# Sheet3_Power_Managment.net
KiCad netlist of a schematic drawn in Altium Designer
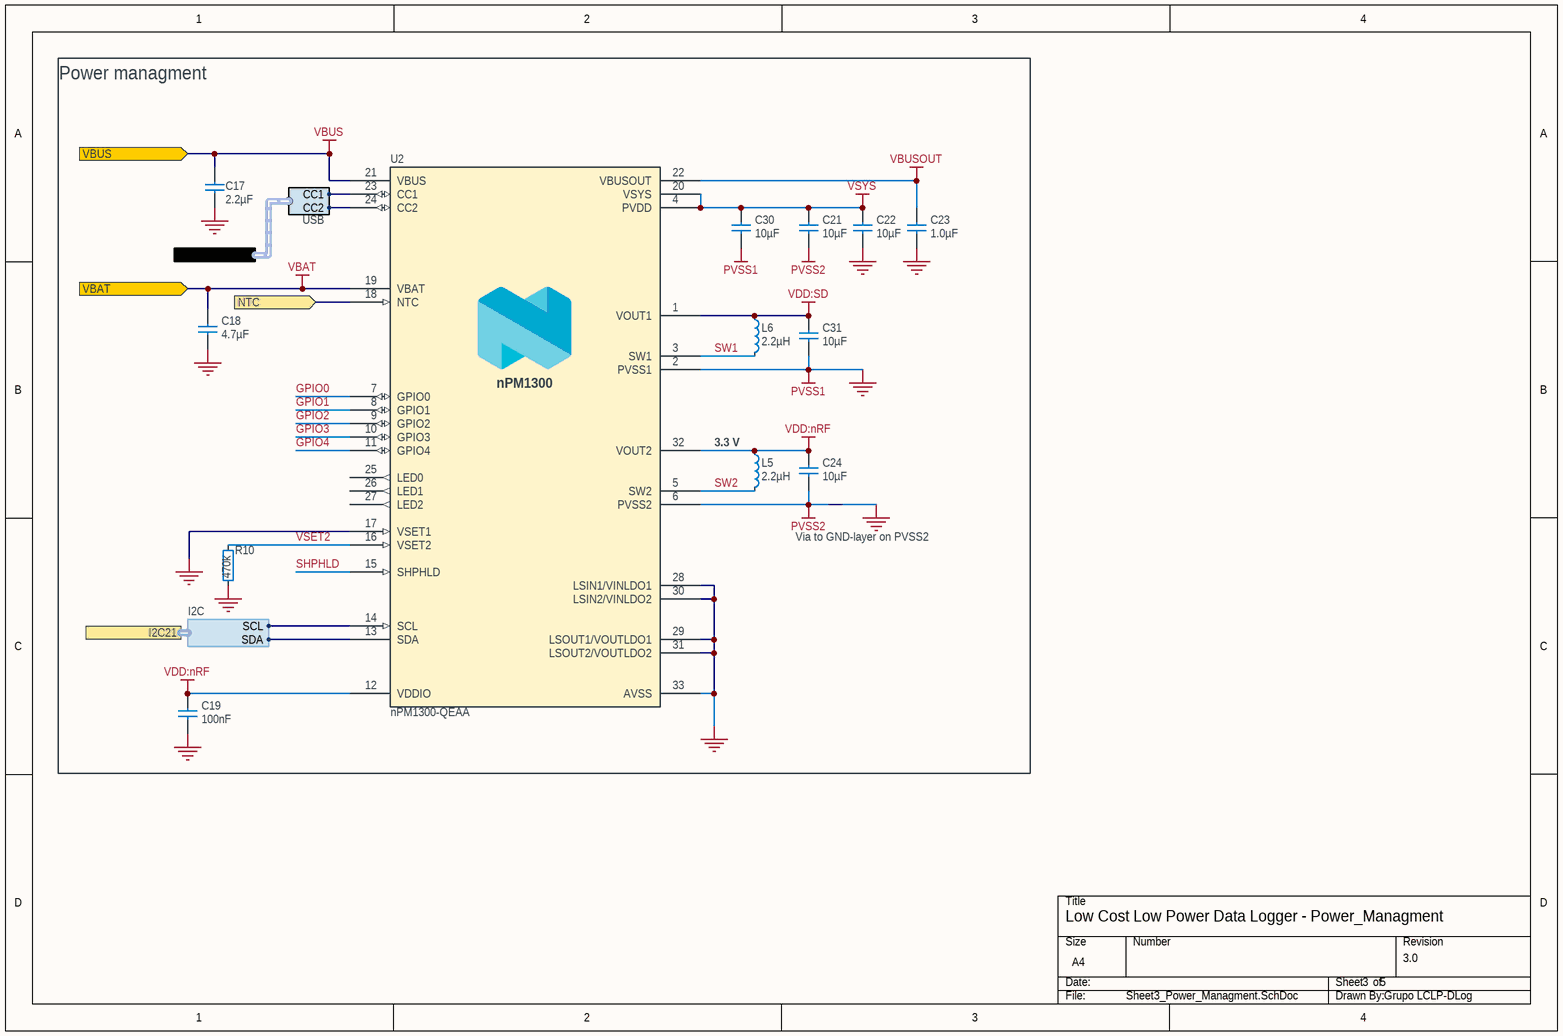
[diagram p0: Sheet3_Power_Managment.SchDoc]

(export (version "E")
  (design (tool "Eeschema 10.0.6"))
  (components
    (comp (ref "C17")
      (value "2.2µF")
      (footprint "LCLP:CAPC1005X04L")
      (description "Capacitor, X5R, ±10%")
      (fields
        (field (name "PART NUMBER") "C0402-2µ2-10V")
        (field (name "MANUFACTURER") "N.A.")
        (field (name "AUTHOR") "rsk")
      )
      (libsource (lib "") (part "CAP_1"))
    )
    (comp (ref "C18")
      (value "4.7µF")
      (footprint "LCLP:CAPC1608X06L")
      (description "Capacitor, Ceramic, X5R, ±10%, 10V")
      (fields
        (field (name "PART NUMBER") "C0603-4µ7-10V-X5R")
        (field (name "MANUFACTURER") "N.A.")
        (field (name "AUTHOR") "rubr")
      )
      (libsource (lib "") (part "CAP_1"))
    )
    (comp (ref "C19")
      (value "100nF")
      (footprint "LCLP:CAPC0603X03L_C")
      (description "Capacitor, X5R, ±10%, 100nF, 16V")
      (fields
        (field (name "PART NUMBER") "C0201-100n")
        (field (name "MANUFACTURER") "N.A.")
        (field (name "AUTHOR") "rsk")
      )
      (libsource (lib "AltiumLib") (part "CAP"))
    )
    (comp (ref "C21")
      (value "10µF")
      (footprint "LCLP:CAPC1608X06L")
      (description "Capacitor, X5R, ±20%")
      (fields
        (field (name "PART NUMBER") "C0603-10µ")
        (field (name "MANUFACTURER") "N.A.")
        (field (name "AUTHOR") "rsk")
      )
      (libsource (lib "AltiumLib") (part "CAP"))
    )
    (comp (ref "C22")
      (value "10µF")
      (footprint "LCLP:CAPC1608X06L")
      (description "Capacitor, X5R, ±20%")
      (fields
        (field (name "PART NUMBER") "C0603-10µ")
        (field (name "MANUFACTURER") "N.A.")
        (field (name "AUTHOR") "rsk")
      )
      (libsource (lib "AltiumLib") (part "CAP"))
    )
    (comp (ref "C23")
      (value "1.0µF")
      (footprint "LCLP:CAPC1608X06L")
      (description "Capacitor, Ceramic, 1.0µF 10V X5R 0603,±10%")
      (fields
        (field (name "PART NUMBER") "C0603-1µ0-10V-X5R")
        (field (name "MANUFACTURER") "N.A.")
        (field (name "AUTHOR") "getr")
      )
      (libsource (lib "AltiumLib") (part "CAP"))
    )
    (comp (ref "C24")
      (value "10µF")
      (footprint "LCLP:CAPC1608X06L")
      (description "Capacitor, X5R, ±20%")
      (fields
        (field (name "PART NUMBER") "C0603-10µ")
        (field (name "MANUFACTURER") "N.A.")
        (field (name "AUTHOR") "rsk")
      )
      (libsource (lib "AltiumLib") (part "CAP"))
    )
    (comp (ref "C30")
      (value "10µF")
      (footprint "LCLP:CAPC1608X06L")
      (description "Capacitor, Ceramic, X5R, ±20%, 25V")
      (fields
        (field (name "PART NUMBER") "C0603-10µ-25V-X5R-GRM188R61E106MA73J")
        (field (name "MANUFACTURER") "Murata")
        (field (name "AUTHOR") "rsk")
      )
      (libsource (lib "") (part "CAP_1"))
    )
    (comp (ref "C31")
      (value "10µF")
      (footprint "LCLP:CAPC1608X06L")
      (description "Capacitor, Ceramic, X5R, ±20%, 25V")
      (fields
        (field (name "PART NUMBER") "C0603-10µ-25V-X5R-GRM188R61E106MA73J")
        (field (name "MANUFACTURER") "Murata")
        (field (name "AUTHOR") "rsk")
      )
      (libsource (lib "") (part "CAP_1"))
    )
    (comp (ref "L5")
      (value "2.2µH")
      (footprint "LCLP:INDC2016X10N")
      (description "Inductor, Irms=2.5A, Isat=2.9A, ±20%, DCR=73mΩ")
      (fields
        (field (name "PART NUMBER") "L0806-2µ2-2500mA-73mOhm-CIGT201610EH2R2MNE")
        (field (name "MANUFACTURER") "Samsung Electro-Mechanics America")
        (field (name "AUTHOR") "rsk")
      )
      (libsource (lib "AltiumLib") (part "IND"))
    )
    (comp (ref "L6")
      (value "2.2µH")
      (footprint "LCLP:INDC2016X10N")
      (description "Inductor, Irms=2.5A, Isat=2.9A, ±20%, DCR=73mΩ")
      (fields
        (field (name "PART NUMBER") "L0806-2µ2-2500mA-73mOhm-CIGT201610EH2R2MNE")
        (field (name "MANUFACTURER") "Samsung Electro-Mechanics")
        (field (name "AUTHOR") "rsk")
      )
      (libsource (lib "AltiumLib") (part "IND"))
    )
    (comp (ref "R10")
      (value "470k")
      (footprint "LCLP:RESC0603X03L_C")
      (description "Resistor, ±1%, 0.05W")
      (fields
        (field (name "PART NUMBER") "R0201-150k")
        (field (name "MANUFACTURER") "N.A.")
        (field (name "AUTHOR") "rsk")
      )
      (libsource (lib "AltiumLib") (part "RES"))
    )
    (comp (ref "U2")
      (value "nPM1300-QEAA")
      (footprint "LCLP:Nordic_QFN50P500X500X90-33N")
      (fields (field (name "MANUFACTURER") "Nordic Semiconductor") (field (name "AUTHOR") "eisk"))
      (libsource (lib "AltiumLib") (part "nPM1300_QEAA"))
    )
  )
  (nets
    (net (code "3") (name "/CC1") (class "Default")
      (node (ref "U2") (pin "23") (pinfunction "CC1_23") (pintype "bidirectional"))
    )
    (net (code "4") (name "/CC2") (class "Default")
      (node (ref "U2") (pin "24") (pinfunction "CC2_24") (pintype "bidirectional"))
    )
    (net (code "5") (name "/GPIO0") (class "Default")
      (node (ref "U2") (pin "7") (pinfunction "GPIO0_7") (pintype "bidirectional"))
    )
    (net (code "6") (name "/GPIO1") (class "Default")
      (node (ref "U2") (pin "8") (pinfunction "GPIO1_8") (pintype "bidirectional"))
    )
    (net (code "7") (name "/GPIO2") (class "Default")
      (node (ref "U2") (pin "9") (pinfunction "GPIO2_9") (pintype "bidirectional"))
    )
    (net (code "8") (name "/GPIO3") (class "Default")
      (node (ref "U2") (pin "10") (pinfunction "GPIO3_10") (pintype "bidirectional"))
    )
    (net (code "9") (name "/GPIO4") (class "Default")
      (node (ref "U2") (pin "11") (pinfunction "GPIO4_11") (pintype "bidirectional"))
    )
    (net (code "10") (name "/NTC") (class "Default")
      (node (ref "U2") (pin "18") (pinfunction "NTC_18") (pintype "input"))
    )
    (net (code "11") (name "/SCL") (class "Default")
      (node (ref "U2") (pin "14") (pinfunction "SCL_14") (pintype "input"))
    )
    (net (code "12") (name "/SDA") (class "Default")
      (node (ref "U2") (pin "13") (pinfunction "SDA_13") (pintype "open_collector"))
    )
    (net (code "13") (name "/SHPHLD") (class "Default")
      (node (ref "U2") (pin "15") (pinfunction "SHPHLD_15") (pintype "input"))
    )
    (net (code "14") (name "/SW1") (class "Default")
      (node (ref "L6") (pin "2") (pinfunction "2_2") (pintype "passive"))
      (node (ref "U2") (pin "3") (pinfunction "SW1_3") (pintype "power_in"))
    )
    (net (code "15") (name "/SW2") (class "Default")
      (node (ref "L5") (pin "2") (pinfunction "2_2") (pintype "passive"))
      (node (ref "U2") (pin "5") (pinfunction "SW2_5") (pintype "power_in"))
    )
    (net (code "16") (name "/VSET2") (class "Default")
      (node (ref "R10") (pin "1") (pinfunction "1_1") (pintype "passive"))
      (node (ref "U2") (pin "16") (pinfunction "VSET2_16") (pintype "input"))
    )
    (net (code "19") (name "GND") (class "Default")
      (node (ref "C17") (pin "1") (pinfunction "1_1") (pintype "passive"))
      (node (ref "C18") (pin "1") (pinfunction "1_1") (pintype "passive"))
      (node (ref "C19") (pin "2") (pinfunction "2_2") (pintype "passive"))
      (node (ref "C21") (pin "1") (pinfunction "1_1") (pintype "passive"))
      (node (ref "C22") (pin "1") (pinfunction "1_1") (pintype "passive"))
      (node (ref "C23") (pin "1") (pinfunction "1_1") (pintype "passive"))
      (node (ref "C24") (pin "1") (pinfunction "1_1") (pintype "passive"))
      (node (ref "C30") (pin "1") (pinfunction "1_1") (pintype "passive"))
      (node (ref "C31") (pin "1") (pinfunction "1_1") (pintype "passive"))
      (node (ref "R10") (pin "2") (pinfunction "2_2") (pintype "passive"))
      (node (ref "U2") (pin "17") (pinfunction "VSET1_17") (pintype "input"))
      (node (ref "U2") (pin "2") (pinfunction "PVSS1_2") (pintype "power_in"))
      (node (ref "U2") (pin "28") (pinfunction "LSIN1/VINLDO1_28") (pintype "power_in"))
      (node (ref "U2") (pin "29") (pinfunction "LSOUT1/VOUTLDO1_29") (pintype "power_in"))
      (node (ref "U2") (pin "30") (pinfunction "LSIN2/VINLDO2_30") (pintype "power_in"))
      (node (ref "U2") (pin "31") (pinfunction "LSOUT2/VOUTLDO2_31") (pintype "power_in"))
      (node (ref "U2") (pin "33") (pinfunction "AVSS_33") (pintype "power_in"))
      (node (ref "U2") (pin "6") (pinfunction "PVSS2_6") (pintype "power_in"))
    )
    (net (code "20") (name "VBAT") (class "Default")
      (node (ref "C18") (pin "2") (pinfunction "2_2") (pintype "passive"))
      (node (ref "U2") (pin "19") (pinfunction "VBAT_19") (pintype "passive"))
    )
    (net (code "21") (name "VBUS") (class "Default")
      (node (ref "C17") (pin "2") (pinfunction "2_2") (pintype "passive"))
      (node (ref "U2") (pin "21") (pinfunction "VBUS_21") (pintype "power_in"))
    )
    (net (code "22") (name "VBUSOUT") (class "Default")
      (node (ref "C23") (pin "2") (pinfunction "2_2") (pintype "passive"))
      (node (ref "U2") (pin "22") (pinfunction "VBUSOUT_22") (pintype "power_in"))
    )
    (net (code "23") (name "VDD:SD") (class "Default")
      (node (ref "C31") (pin "2") (pinfunction "2_2") (pintype "passive"))
      (node (ref "L6") (pin "1") (pinfunction "1_1") (pintype "passive"))
      (node (ref "U2") (pin "1") (pinfunction "VOUT1_1") (pintype "power_in"))
    )
    (net (code "24") (name "VDD:nRF") (class "Default")
      (node (ref "C19") (pin "1") (pinfunction "1_1") (pintype "passive"))
      (node (ref "C24") (pin "2") (pinfunction "2_2") (pintype "passive"))
      (node (ref "L5") (pin "1") (pinfunction "1_1") (pintype "passive"))
      (node (ref "U2") (pin "12") (pinfunction "VDDIO_12") (pintype "power_in"))
      (node (ref "U2") (pin "32") (pinfunction "VOUT2_32") (pintype "power_in"))
    )
    (net (code "25") (name "VSYS") (class "Default")
      (node (ref "C21") (pin "2") (pinfunction "2_2") (pintype "passive"))
      (node (ref "C22") (pin "2") (pinfunction "2_2") (pintype "passive"))
      (node (ref "C30") (pin "2") (pinfunction "2_2") (pintype "passive"))
      (node (ref "U2") (pin "20") (pinfunction "VSYS_20") (pintype "power_in"))
      (node (ref "U2") (pin "4") (pinfunction "PVDD_4") (pintype "power_in"))
    )
    (net (code "26") (name "unconnected-(U2-LED0-Pad25)") (class "Default")
      (node (ref "U2") (pin "25") (pinfunction "LED0_25") (pintype "output"))
    )
    (net (code "27") (name "unconnected-(U2-LED1-Pad26)") (class "Default")
      (node (ref "U2") (pin "26") (pinfunction "LED1_26") (pintype "output"))
    )
    (net (code "28") (name "unconnected-(U2-LED2-Pad27)") (class "Default")
      (node (ref "U2") (pin "27") (pinfunction "LED2_27") (pintype "output"))
    )
  )
)
